# Main.net
KiCad netlist of a schematic drawn in Altium Designer
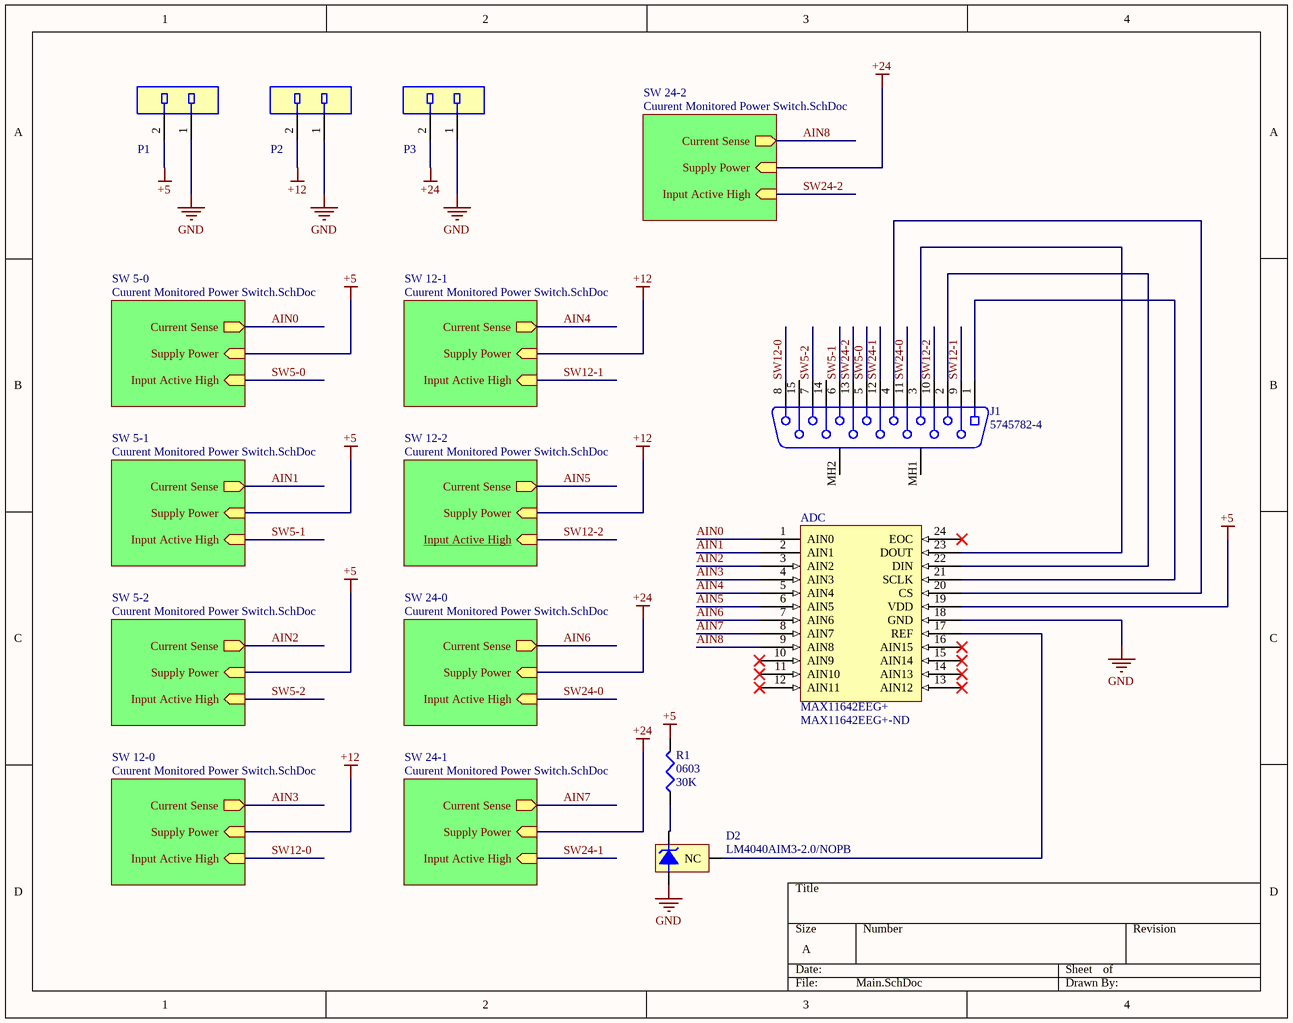
[diagram p0: Main.SchDoc]

(export (version "E")
  (design (tool "Eeschema 10.0.6"))
  (components
    (comp (ref "ADC")
      (value "MAX11642EEG+")
      (footprint "QSOP-24")
      (description "ADC Single SAR 300ksps 8-bit Serial 24-Pin QSOP")
      (fields (field (name "MANUFACTURER") "Maxim") (field (name "SUPPLIER PART NUMBER 1") "MAX11642EEG+-ND"))
      (libsource (lib "Main Library") (part "MAX11642EEG+"))
    )
    (comp (ref "D2")
      (value "LM4040AIM3-2.0/NOPB")
      (footprint "MF03A_L")
      (description "Precision Micropower Shunt Voltage Reference, 3-pin SOT-23, Pb-Free")
      (fields
        (field (name "MANUFACTURER") "National Semiconductor")
        (field (name "MANUFACTURER PART NUMBER") "LM4040EIM7-2.0/NOPB")
      )
      (libsource (lib "Altium Content Vault") (part "PM-REF-LM4040-SOT3"))
    )
    (comp (ref "J1")
      (value "5745782-4")
      (footprint "TECO-5745782-4_V")
      (fields (field (name "MANUFACTURER") "TE Connectivity"))
      (libsource (lib "Altium Content Vault") (part "CN-2S-2F-D15"))
    )
    (comp (ref "P1")
      (value "70553-0001")
      (footprint "Molex_70553-0001_MFG")
      (description "Molex Connector 2 pin 90 degree through hole .100")
      (libsource (lib "Main Library") (part "70553-0001"))
    )
    (comp (ref "P2")
      (value "70553-0001")
      (footprint "Molex_70553-0001_MFG")
      (description "Molex Connector 2 pin 90 degree through hole .100")
      (libsource (lib "Main Library") (part "70553-0001"))
    )
    (comp (ref "P3")
      (value "70553-0001")
      (footprint "Molex_70553-0001_MFG")
      (description "Molex Connector 2 pin 90 degree through hole .100")
      (libsource (lib "Main Library") (part "70553-0001"))
    )
    (comp (ref "R1")
      (value "0603")
      (footprint "J1-0603")
      (description "Resistor")
      (fields (field (name "ALTIUM_VALUE") "30K") (field (name "PUBLISHER") "Altium Limited"))
      (libsource (lib "Miscellaneous Devices") (part "Res3"))
    )
  )
  (nets
    (net (code "1") (name "+5") (class "Default")
      (node (ref "ADC") (pin "19") (pinfunction "VDD_19") (pintype "input"))
      (node (ref "P1") (pin "2") (pinfunction "2_2") (pintype "passive"))
      (node (ref "R1") (pin "2") (pinfunction "2_2") (pintype "passive"))
    )
    (net (code "2") (name "+12") (class "Default")
      (node (ref "P2") (pin "2") (pinfunction "2_2") (pintype "passive"))
    )
    (net (code "3") (name "+24") (class "Default")
      (node (ref "P3") (pin "2") (pinfunction "2_2") (pintype "passive"))
    )
    (net (code "4") (name "/AIN0") (class "Default")
      (node (ref "ADC") (pin "1") (pinfunction "AIN0_1") (pintype "passive"))
    )
    (net (code "5") (name "/AIN1") (class "Default")
      (node (ref "ADC") (pin "2") (pinfunction "AIN1_2") (pintype "passive"))
    )
    (net (code "6") (name "/AIN2") (class "Default")
      (node (ref "ADC") (pin "3") (pinfunction "AIN2_3") (pintype "input"))
    )
    (net (code "7") (name "/AIN3") (class "Default")
      (node (ref "ADC") (pin "4") (pinfunction "AIN3_4") (pintype "input"))
    )
    (net (code "8") (name "/AIN4") (class "Default")
      (node (ref "ADC") (pin "5") (pinfunction "AIN4_5") (pintype "input"))
    )
    (net (code "9") (name "/AIN5") (class "Default")
      (node (ref "ADC") (pin "6") (pinfunction "AIN5_6") (pintype "input"))
    )
    (net (code "10") (name "/AIN6") (class "Default")
      (node (ref "ADC") (pin "7") (pinfunction "AIN6_7") (pintype "input"))
    )
    (net (code "11") (name "/AIN7") (class "Default")
      (node (ref "ADC") (pin "8") (pinfunction "AIN7_8") (pintype "input"))
    )
    (net (code "12") (name "/AIN8") (class "Default")
      (node (ref "ADC") (pin "9") (pinfunction "AIN8_9") (pintype "input"))
    )
    (net (code "13") (name "/SW5-0") (class "Default")
      (node (ref "J1") (pin "5") (pinfunction "5_5") (pintype "passive"))
    )
    (net (code "14") (name "/SW5-1") (class "Default")
      (node (ref "J1") (pin "6") (pinfunction "6_6") (pintype "passive"))
    )
    (net (code "15") (name "/SW5-2") (class "Default")
      (node (ref "J1") (pin "7") (pinfunction "7_7") (pintype "passive"))
    )
    (net (code "16") (name "/SW12-0") (class "Default")
      (node (ref "J1") (pin "8") (pinfunction "8_8") (pintype "passive"))
    )
    (net (code "17") (name "/SW12-1") (class "Default")
      (node (ref "J1") (pin "9") (pinfunction "9_9") (pintype "passive"))
    )
    (net (code "18") (name "/SW12-2") (class "Default")
      (node (ref "J1") (pin "10") (pinfunction "10_10") (pintype "passive"))
    )
    (net (code "19") (name "/SW24-0") (class "Default")
      (node (ref "J1") (pin "11") (pinfunction "11_11") (pintype "passive"))
    )
    (net (code "20") (name "/SW24-1") (class "Default")
      (node (ref "J1") (pin "12") (pinfunction "12_12") (pintype "passive"))
    )
    (net (code "21") (name "/SW24-2") (class "Default")
      (node (ref "J1") (pin "13") (pinfunction "13_13") (pintype "passive"))
    )
    (net (code "22") (name "GND") (class "Default")
      (node (ref "ADC") (pin "18") (pinfunction "GND_18") (pintype "input"))
      (node (ref "D2") (pin "2") (pinfunction "-V_2") (pintype "passive"))
      (node (ref "P1") (pin "1") (pinfunction "1_1") (pintype "passive"))
      (node (ref "P2") (pin "1") (pinfunction "1_1") (pintype "passive"))
      (node (ref "P3") (pin "1") (pinfunction "1_1") (pintype "passive"))
    )
    (net (code "23") (name "Net-(ADC-CS)") (class "Default")
      (node (ref "ADC") (pin "20") (pinfunction "CS_20") (pintype "input"))
      (node (ref "J1") (pin "4") (pinfunction "4_4") (pintype "passive"))
    )
    (net (code "24") (name "Net-(ADC-DIN)") (class "Default")
      (node (ref "ADC") (pin "22") (pinfunction "DIN_22") (pintype "input"))
      (node (ref "J1") (pin "2") (pinfunction "2_2") (pintype "passive"))
    )
    (net (code "25") (name "Net-(ADC-DOUT)") (class "Default")
      (node (ref "ADC") (pin "23") (pinfunction "DOUT_23") (pintype "input"))
      (node (ref "J1") (pin "3") (pinfunction "3_3") (pintype "passive"))
    )
    (net (code "26") (name "Net-(ADC-REF)") (class "Default")
      (node (ref "ADC") (pin "17") (pinfunction "REF_17") (pintype "input"))
      (node (ref "D2") (pin "3") (pinfunction "NC_3") (pintype "passive"))
    )
    (net (code "27") (name "Net-(ADC-SCLK)") (class "Default")
      (node (ref "ADC") (pin "21") (pinfunction "SCLK_21") (pintype "input"))
      (node (ref "J1") (pin "1") (pinfunction "1_1") (pintype "passive"))
    )
    (net (code "28") (name "Net-(D2-+V)") (class "Default")
      (node (ref "D2") (pin "1") (pinfunction "+V_1") (pintype "passive"))
      (node (ref "R1") (pin "1") (pinfunction "1_1") (pintype "passive"))
    )
    (net (code "29") (name "unconnected-(ADC-AIN9-Pad10)") (class "Default")
      (node (ref "ADC") (pin "10") (pinfunction "AIN9_10") (pintype "input+no_connect"))
    )
    (net (code "30") (name "unconnected-(ADC-AIN10-Pad11)") (class "Default")
      (node (ref "ADC") (pin "11") (pinfunction "AIN10_11") (pintype "input+no_connect"))
    )
    (net (code "31") (name "unconnected-(ADC-AIN11-Pad12)") (class "Default")
      (node (ref "ADC") (pin "12") (pinfunction "AIN11_12") (pintype "input+no_connect"))
    )
    (net (code "32") (name "unconnected-(ADC-AIN12-Pad13)") (class "Default")
      (node (ref "ADC") (pin "13") (pinfunction "AIN12_13") (pintype "input+no_connect"))
    )
    (net (code "33") (name "unconnected-(ADC-AIN13-Pad14)") (class "Default")
      (node (ref "ADC") (pin "14") (pinfunction "AIN13_14") (pintype "input+no_connect"))
    )
    (net (code "34") (name "unconnected-(ADC-AIN14-Pad15)") (class "Default")
      (node (ref "ADC") (pin "15") (pinfunction "AIN14_15") (pintype "input+no_connect"))
    )
    (net (code "35") (name "unconnected-(ADC-AIN15-Pad16)") (class "Default")
      (node (ref "ADC") (pin "16") (pinfunction "AIN15_16") (pintype "input+no_connect"))
    )
    (net (code "36") (name "unconnected-(ADC-EOC-Pad24)") (class "Default")
      (node (ref "ADC") (pin "24") (pinfunction "EOC_24") (pintype "input+no_connect"))
    )
    (net (code "37") (name "unconnected-(J1-Pad14)") (class "Default")
      (node (ref "J1") (pin "14") (pinfunction "14_14") (pintype "passive"))
    )
    (net (code "38") (name "unconnected-(J1-Pad15)") (class "Default")
      (node (ref "J1") (pin "15") (pinfunction "15_15") (pintype "passive"))
    )
    (net (code "39") (name "unconnected-(J1-PadMH1)") (class "Default")
      (node (ref "J1") (pin "MH1") (pinfunction "MH1_MH1") (pintype "passive"))
    )
    (net (code "40") (name "unconnected-(J1-PadMH2)") (class "Default")
      (node (ref "J1") (pin "MH2") (pinfunction "MH2_MH2") (pintype "passive"))
    )
  )
)
